# LiDAR_Lite_Interface_HardSwitch.net
KiCad netlist of a schematic drawn in EAGLE
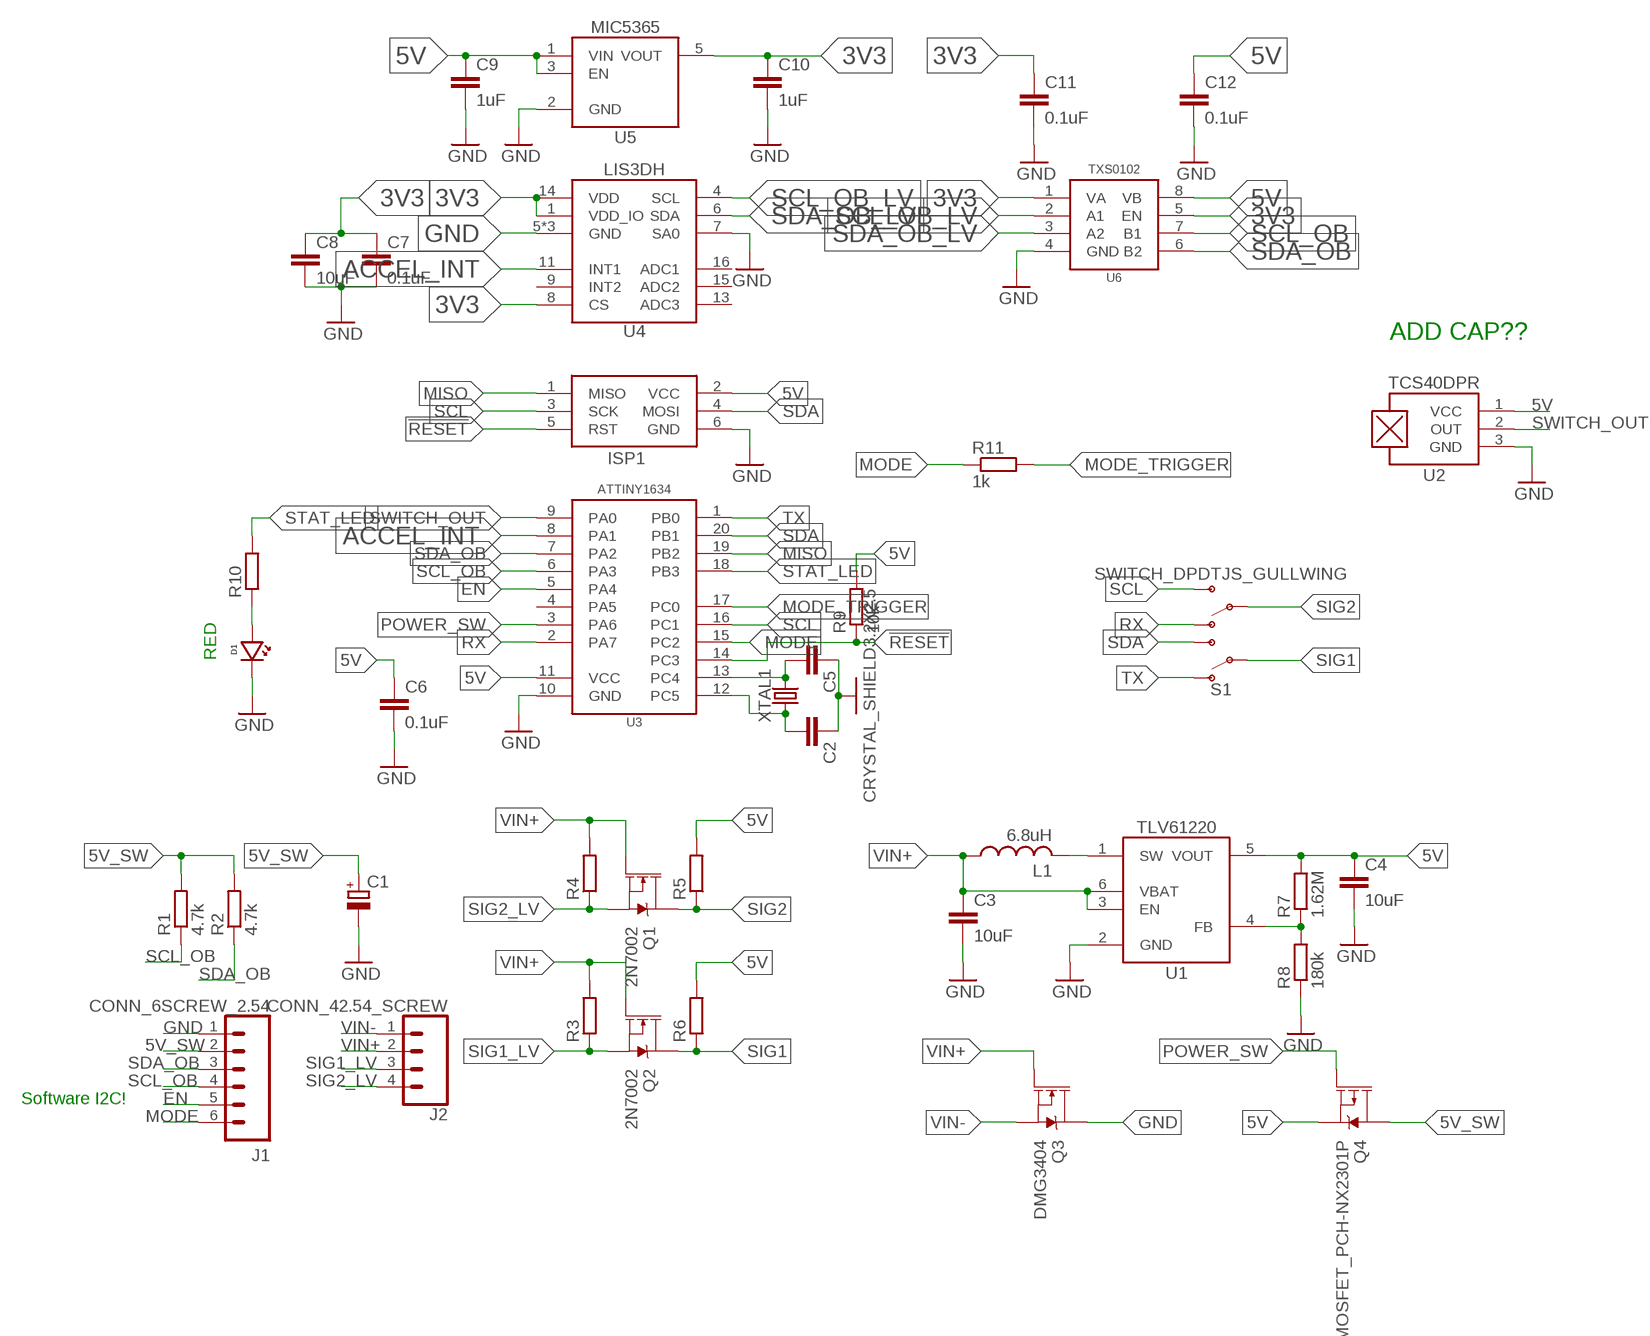
[diagram p0: schematic, sheet 1]

(export (version "E")
  (design (tool "Eeschema 10.0.6"))
  (components
    (comp (ref "C1")
      (value "CPOL-EUUW-10X10")
      (footprint "eagle-import:UW-10X10_NICHICON")
      (fields (field (name "MF") "Nichicon") (field (name "MPN") "UWT1C681MNL1GS"))
      (libsource (lib "eagle-import") (part "CPOL-EUUW-10X10"))
    )
    (comp (ref "C2")
      (value "C-EU10PFC0603")
      (footprint "eagle-import:C0603")
      (fields (field (name "MF") "Yageo") (field (name "MPN") "CC0603JRNPO9BN100CC0603JRNPO9BN100"))
      (libsource (lib "eagle-import") (part "C-EUC060310PF"))
    )
    (comp (ref "C3")
      (value "10uF")
      (footprint "eagle-import:C0805")
      (fields (field (name "MF") "Murata") (field (name "MPN") "GRM21BR61C106KE15K"))
      (libsource (lib "eagle-import") (part "C-EUC080510UF"))
    )
    (comp (ref "C4")
      (value "10uF")
      (footprint "eagle-import:C0805")
      (fields (field (name "MF") "Murata") (field (name "MPN") "GRM21BR61C106KE15K"))
      (libsource (lib "eagle-import") (part "C-EUC080510UF"))
    )
    (comp (ref "C5")
      (value "C-EU10PFC0603")
      (footprint "eagle-import:C0603")
      (fields (field (name "MF") "Yageo") (field (name "MPN") "CC0603JRNPO9BN100CC0603JRNPO9BN100"))
      (libsource (lib "eagle-import") (part "C-EUC060310PF"))
    )
    (comp (ref "C6")
      (value "0.1uF")
      (footprint "eagle-import:C0603")
      (fields (field (name "MF") "Murata") (field (name "MPN") "GCM188R71E104KA57D"))
      (libsource (lib "eagle-import") (part "C-EUC06030.1UF"))
    )
    (comp (ref "C7")
      (value "0.1uF")
      (footprint "eagle-import:C0805")
      (fields (field (name "MF") "Murata") (field (name "MPN") "GRM21BR61C106KE15K"))
      (libsource (lib "eagle-import") (part "C-EUC080510UF"))
    )
    (comp (ref "C8")
      (value "10uF")
      (footprint "eagle-import:C0603")
      (fields (field (name "MF") "Murata") (field (name "MPN") "GCM188R71E104KA57D"))
      (libsource (lib "eagle-import") (part "C-EUC06030.1UF"))
    )
    (comp (ref "C9")
      (value "1uF")
      (footprint "eagle-import:C0603")
      (fields (field (name "MF") "Murata") (field (name "MPN") "GRM188R61C105KA12D"))
      (libsource (lib "eagle-import") (part "C-EUC06031UF"))
    )
    (comp (ref "C10")
      (value "1uF")
      (footprint "eagle-import:C0603")
      (fields (field (name "MF") "Murata") (field (name "MPN") "GRM188R61C105KA12D"))
      (libsource (lib "eagle-import") (part "C-EUC06031UF"))
    )
    (comp (ref "C11")
      (value "0.1uF")
      (footprint "eagle-import:C0402")
      (fields (field (name "MF") "Murata") (field (name "MPN") "GCM155R71C104KA55D"))
      (libsource (lib "eagle-import") (part "C-EUC04020.1UF"))
    )
    (comp (ref "C12")
      (value "0.1uF")
      (footprint "eagle-import:C0402")
      (fields (field (name "MF") "Murata") (field (name "MPN") "GCM155R71C104KA55D"))
      (libsource (lib "eagle-import") (part "C-EUC04020.1UF"))
    )
    (comp (ref "D1")
      (value "LED0603")
      (footprint "eagle-import:LED_0603")
      (fields
        (field (name "DIGIKEY") "732-4978-1-ND")
        (field (name "MF") "Wurth")
        (field (name "MPN") "150060RS75000")
      )
      (libsource (lib "eagle-import") (part "LED0603"))
    )
    (comp (ref "ISP1")
      (value "AVRISP-6")
      (footprint "eagle-import:AVRISP")
      (libsource (lib "eagle-import") (part "AVRISP-6"))
    )
    (comp (ref "J1")
      (value "CONN_6SCREW_2.54")
      (footprint "eagle-import:1X06_SCREW")
      (fields (field (name "MF") "OnShore") (field (name "MPN") "OSTVN06A150"))
      (libsource (lib "eagle-import") (part "CONN_6SCREW_2.54"))
    )
    (comp (ref "J2")
      (value "CONN_42.54_SCREW")
      (footprint "eagle-import:1X04_SCREW")
      (fields (field (name "MF") "On Shore") (field (name "MPN") "OSTVN04A150"))
      (libsource (lib "eagle-import") (part "CONN_42.54_SCREW"))
    )
    (comp (ref "L1")
      (value "6.8uH")
      (footprint "eagle-import:1008")
      (fields (field (name "MF") "Wurth") (field (name "MPN") "74438323068"))
      (libsource (lib "eagle-import") (part "INDUCTOR1008"))
    )
    (comp (ref "Q1")
      (value "2N7002")
      (footprint "eagle-import:SOT23-3")
      (fields (field (name "MF") "Nexperia") (field (name "MPN") "2N7002P,215"))
      (libsource (lib "eagle-import") (part "MOSFET-NCH-2N7002P"))
    )
    (comp (ref "Q2")
      (value "2N7002")
      (footprint "eagle-import:SOT23-3")
      (fields (field (name "MF") "Nexperia") (field (name "MPN") "2N7002P,215"))
      (libsource (lib "eagle-import") (part "MOSFET-NCH-2N7002P"))
    )
    (comp (ref "Q3")
      (value "DMG3404")
      (footprint "eagle-import:SOT23-3")
      (fields (field (name "MF") "Diodes Incorporated") (field (name "MPN") "DMG3404L-7"))
      (libsource (lib "eagle-import") (part "MOSFET-NCH-DMG3404L"))
    )
    (comp (ref "Q4")
      (value "MOSFET_PCH-NX2301P")
      (footprint "eagle-import:SOT23-3")
      (fields (field (name "MF") "Nexperia") (field (name "MPN") "NX2301P,215"))
      (libsource (lib "eagle-import") (part "MOSFET_PCH-NX2301P"))
    )
    (comp (ref "R1")
      (value "4.7k")
      (footprint "eagle-import:R0603")
      (fields (field (name "MF") "Yageo") (field (name "MPN") "RC0603FR-074K7L"))
      (libsource (lib "eagle-import") (part "R-EU_R06034.7K"))
    )
    (comp (ref "R2")
      (value "4.7k")
      (footprint "eagle-import:R0603")
      (fields (field (name "MF") "Yageo") (field (name "MPN") "RC0603FR-074K7L"))
      (libsource (lib "eagle-import") (part "R-EU_R06034.7K"))
    )
    (comp (ref "R3")
      (value "R-EU_10KR0603")
      (footprint "eagle-import:R0603")
      (fields
        (field (name "MF") "Yageo")
        (field (name "MPN") "RC0603FR-0710KL")
        (field (name "VALUE_PART") "10k")
      )
      (libsource (lib "eagle-import") (part "R-EU_R060310K"))
    )
    (comp (ref "R4")
      (value "R-EU_10KR0603")
      (footprint "eagle-import:R0603")
      (fields
        (field (name "MF") "Yageo")
        (field (name "MPN") "RC0603FR-0710KL")
        (field (name "VALUE_PART") "10k")
      )
      (libsource (lib "eagle-import") (part "R-EU_R060310K"))
    )
    (comp (ref "R5")
      (value "R-EU_10KR0603")
      (footprint "eagle-import:R0603")
      (fields
        (field (name "MF") "Yageo")
        (field (name "MPN") "RC0603FR-0710KL")
        (field (name "VALUE_PART") "10k")
      )
      (libsource (lib "eagle-import") (part "R-EU_R060310K"))
    )
    (comp (ref "R6")
      (value "R-EU_10KR0603")
      (footprint "eagle-import:R0603")
      (fields
        (field (name "MF") "Yageo")
        (field (name "MPN") "RC0603FR-0710KL")
        (field (name "VALUE_PART") "10k")
      )
      (libsource (lib "eagle-import") (part "R-EU_R060310K"))
    )
    (comp (ref "R7")
      (value "1.62M")
      (footprint "eagle-import:R0603")
      (fields (field (name "MF") "Stackpole") (field (name "MPN") "RMCF0603FT1M62"))
      (libsource (lib "eagle-import") (part "R-EU_R06031.62M"))
    )
    (comp (ref "R8")
      (value "180k")
      (footprint "eagle-import:R0603")
      (fields (field (name "MF") "Panasonic") (field (name "MPN") "ERJ-3EKF1803V"))
      (libsource (lib "eagle-import") (part "R-EU_R0603180K"))
    )
    (comp (ref "R9")
      (value "10k")
      (footprint "eagle-import:R0603")
      (fields (field (name "MF") "Yageo") (field (name "MPN") "RC0603FR-0710KL"))
      (libsource (lib "eagle-import") (part "R-EU_R060310K"))
    )
    (comp (ref "R10")
      (value "R-EU_330R0603")
      (footprint "eagle-import:R0603")
      (fields
        (field (name "MF") "Yageo")
        (field (name "MPN") "RC0603FR-07330RL")
        (field (name "VALUE_PART") "330")
      )
      (libsource (lib "eagle-import") (part "R-EU_R0603330"))
    )
    (comp (ref "R11")
      (value "1k")
      (footprint "eagle-import:R0603")
      (fields (field (name "MF") "Yageo") (field (name "MPN") "AC0603FR-071KL"))
      (libsource (lib "eagle-import") (part "R-EU_R06031K"))
    )
    (comp (ref "S1")
      (value "SWITCH_DPDTJS_GULLWING")
      (footprint "eagle-import:JS202011SCQN")
      (fields (field (name "MF") "C&K") (field (name "MPN") "JS202011SCQN"))
      (libsource (lib "eagle-import") (part "SWITCH_DPDTJS_GULLWING"))
    )
    (comp (ref "U1")
      (value "TLV61220DBV")
      (footprint "eagle-import:DBV_R-PDSO-G6")
      (fields (field (name "MF") "TI") (field (name "MPN") "TLV61220DBVR"))
      (libsource (lib "eagle-import") (part "TLV61220DBV"))
    )
    (comp (ref "U2")
      (value "TCS40DPRSOT23")
      (footprint "eagle-import:SOT23-3")
      (fields
        (field (name "DISP") "TCS40DPR")
        (field (name "MF") "Toshiba")
        (field (name "MPN") "TCS40DPR,LF")
      )
      (libsource (lib "eagle-import") (part "TCS40DPRSOT23"))
    )
    (comp (ref "U3")
      (value "ATTINY1634SOIC")
      (footprint "eagle-import:SO-20DW")
      (fields (field (name "MF") "Atmel") (field (name "MPN") "ATTINY1634-SUR"))
      (libsource (lib "eagle-import") (part "ATTINY1634SOIC"))
    )
    (comp (ref "U4")
      (value "LIS3DHLGA")
      (footprint "eagle-import:LGA-16")
      (fields (field (name "MF") "ST") (field (name "MPN") "LIS3DHTR"))
      (libsource (lib "eagle-import") (part "LIS3DHLGA"))
    )
    (comp (ref "U5")
      (value "MIC53653.3SC70")
      (footprint "eagle-import:DCK_R-PDSO-G5")
      (fields (field (name "MF") "Microchip") (field (name "MPN") "MIC5365-3.3YC5-TR"))
      (libsource (lib "eagle-import") (part "MIC5365SC703.3"))
    )
    (comp (ref "U6")
      (value "TXS0102DQM")
      (footprint "eagle-import:DQM_R-PX2SON-N8")
      (fields (field (name "MF") "TI") (field (name "MPN") "TXS0102DQMR"))
      (libsource (lib "eagle-import") (part "TXS0102DQM"))
    )
    (comp (ref "XTAL1")
      (value "CRYSTAL_SHIELD3.2X2.5")
      (footprint "eagle-import:CRYSTAL_3.2X2.5_4-SMD")
      (fields (field (name "MF") "Abricon") (field (name "MPN") "ABM8G-12.000MHZ-4Y-T3"))
      (libsource (lib "eagle-import") (part "CRYSTAL_SHIELD3.2X2.5"))
    )
  )
  (nets
    (net (code "1") (name "/~{RESET}") (class "Default")
      (node (ref "ISP1") (pin "5") (pinfunction "RST_5") (pintype "output"))
      (node (ref "R9") (pin "1") (pinfunction "1_1") (pintype "passive"))
      (node (ref "U3") (pin "14") (pinfunction "PC3_14") (pintype "bidirectional"))
    )
    (net (code "2") (name "3V3") (class "Default")
      (node (ref "C10") (pin "1") (pinfunction "1_1") (pintype "passive"))
      (node (ref "C11") (pin "1") (pinfunction "1_1") (pintype "passive"))
      (node (ref "C7") (pin "1") (pinfunction "1_1") (pintype "passive"))
      (node (ref "C8") (pin "1") (pinfunction "1_1") (pintype "passive"))
      (node (ref "U4") (pin "1") (pinfunction "VDD_IO_1") (pintype "bidirectional"))
      (node (ref "U4") (pin "14") (pinfunction "VDD_14") (pintype "bidirectional"))
      (node (ref "U4") (pin "8") (pinfunction "CS_8") (pintype "bidirectional"))
      (node (ref "U5") (pin "5") (pinfunction "VOUT_5") (pintype "power_in"))
      (node (ref "U6") (pin "1") (pinfunction "VA_1") (pintype "power_in"))
      (node (ref "U6") (pin "5") (pinfunction "EN_5") (pintype "input"))
    )
    (net (code "3") (name "5V") (class "Default")
      (node (ref "C12") (pin "1") (pinfunction "1_1") (pintype "passive"))
      (node (ref "C4") (pin "1") (pinfunction "1_1") (pintype "passive"))
      (node (ref "C6") (pin "1") (pinfunction "1_1") (pintype "passive"))
      (node (ref "C9") (pin "1") (pinfunction "1_1") (pintype "passive"))
      (node (ref "ISP1") (pin "2") (pinfunction "VCC_2") (pintype "power_in"))
      (node (ref "Q4") (pin "2") (pinfunction "S_2") (pintype "bidirectional"))
      (node (ref "R5") (pin "2") (pinfunction "2_2") (pintype "passive"))
      (node (ref "R6") (pin "2") (pinfunction "2_2") (pintype "passive"))
      (node (ref "R7") (pin "2") (pinfunction "2_2") (pintype "passive"))
      (node (ref "R9") (pin "2") (pinfunction "2_2") (pintype "passive"))
      (node (ref "U1") (pin "5") (pinfunction "VOUT_5") (pintype "power_in"))
      (node (ref "U2") (pin "1") (pinfunction "VCC_1") (pintype "power_in"))
      (node (ref "U3") (pin "11") (pinfunction "VCC_11") (pintype "power_in"))
      (node (ref "U5") (pin "1") (pinfunction "VIN_1") (pintype "power_in"))
      (node (ref "U5") (pin "3") (pinfunction "EN_3") (pintype "input"))
      (node (ref "U6") (pin "8") (pinfunction "VB_8") (pintype "power_in"))
    )
    (net (code "4") (name "5V_SW") (class "Default")
      (node (ref "C1") (pin "+") (pinfunction "+_+") (pintype "passive"))
      (node (ref "J1") (pin "2") (pinfunction "2_2") (pintype "passive"))
      (node (ref "Q4") (pin "3") (pinfunction "D_3") (pintype "bidirectional"))
      (node (ref "R1") (pin "2") (pinfunction "2_2") (pintype "passive"))
      (node (ref "R2") (pin "2") (pinfunction "2_2") (pintype "passive"))
    )
    (net (code "5") (name "ACCEL_INT") (class "Default")
      (node (ref "U3") (pin "8") (pinfunction "PA1_8") (pintype "bidirectional"))
      (node (ref "U4") (pin "11") (pinfunction "INT1_11") (pintype "bidirectional"))
    )
    (net (code "6") (name "EN") (class "Default")
      (node (ref "J1") (pin "5") (pinfunction "5_5") (pintype "passive"))
      (node (ref "U3") (pin "5") (pinfunction "PA4_5") (pintype "bidirectional"))
    )
    (net (code "7") (name "GND") (class "Default")
      (node (ref "C1") (pin "-") (pinfunction "-_-") (pintype "passive"))
      (node (ref "C10") (pin "2") (pinfunction "2_2") (pintype "passive"))
      (node (ref "C11") (pin "2") (pinfunction "2_2") (pintype "passive"))
      (node (ref "C12") (pin "2") (pinfunction "2_2") (pintype "passive"))
      (node (ref "C2") (pin "1") (pinfunction "1_1") (pintype "passive"))
      (node (ref "C3") (pin "2") (pinfunction "2_2") (pintype "passive"))
      (node (ref "C4") (pin "2") (pinfunction "2_2") (pintype "passive"))
      (node (ref "C5") (pin "1") (pinfunction "1_1") (pintype "passive"))
      (node (ref "C6") (pin "2") (pinfunction "2_2") (pintype "passive"))
      (node (ref "C7") (pin "2") (pinfunction "2_2") (pintype "passive"))
      (node (ref "C8") (pin "2") (pinfunction "2_2") (pintype "passive"))
      (node (ref "C9") (pin "2") (pinfunction "2_2") (pintype "passive"))
      (node (ref "D1") (pin "CATHODE") (pinfunction "CATHODE_CATHODE") (pintype "power_in"))
      (node (ref "ISP1") (pin "6") (pinfunction "GND_6") (pintype "power_in"))
      (node (ref "J1") (pin "1") (pinfunction "1_1") (pintype "passive"))
      (node (ref "Q3") (pin "3") (pinfunction "D_3") (pintype "bidirectional"))
      (node (ref "R8") (pin "1") (pinfunction "1_1") (pintype "passive"))
      (node (ref "U1") (pin "2") (pinfunction "GND_2") (pintype "power_in"))
      (node (ref "U2") (pin "3") (pinfunction "GND_3") (pintype "power_in"))
      (node (ref "U3") (pin "10") (pinfunction "GND_10") (pintype "power_in"))
      (node (ref "U4") (pin "10") (pinfunction "GND_10") (pintype "bidirectional"))
      (node (ref "U4") (pin "12") (pinfunction "GND_12") (pintype "bidirectional"))
      (node (ref "U4") (pin "5") (pinfunction "GND_5") (pintype "bidirectional"))
      (node (ref "U4") (pin "7") (pinfunction "SA0_7") (pintype "bidirectional"))
      (node (ref "U5") (pin "2") (pinfunction "GND_2") (pintype "power_in"))
      (node (ref "U6") (pin "4") (pinfunction "GND_4") (pintype "power_in"))
      (node (ref "XTAL1") (pin "2") (pinfunction "GND_2") (pintype "power_in"))
      (node (ref "XTAL1") (pin "4") (pinfunction "GND_4") (pintype "power_in"))
    )
    (net (code "8") (name "MISO") (class "Default")
      (node (ref "ISP1") (pin "1") (pinfunction "MISO_1") (pintype "input"))
      (node (ref "U3") (pin "19") (pinfunction "PB2_19") (pintype "bidirectional"))
    )
    (net (code "9") (name "MODE") (class "Default")
      (node (ref "J1") (pin "6") (pinfunction "6_6") (pintype "passive"))
      (node (ref "R11") (pin "1") (pinfunction "1_1") (pintype "passive"))
      (node (ref "U3") (pin "15") (pinfunction "PC2_15") (pintype "bidirectional"))
    )
    (net (code "10") (name "MODE_TRIGGER") (class "Default")
      (node (ref "R11") (pin "2") (pinfunction "2_2") (pintype "passive"))
      (node (ref "U3") (pin "17") (pinfunction "PC0_17") (pintype "bidirectional"))
    )
    (net (code "11") (name "Net-(D1-PadANODE)") (class "Default")
      (node (ref "D1") (pin "ANODE") (pinfunction "ANODE_ANODE") (pintype "power_in"))
      (node (ref "R10") (pin "1") (pinfunction "1_1") (pintype "passive"))
    )
    (net (code "12") (name "Net-(U1-FB)") (class "Default")
      (node (ref "R7") (pin "1") (pinfunction "1_1") (pintype "passive"))
      (node (ref "R8") (pin "2") (pinfunction "2_2") (pintype "passive"))
      (node (ref "U1") (pin "4") (pinfunction "FB_4") (pintype "input"))
    )
    (net (code "13") (name "Net-(U1-SW)") (class "Default")
      (node (ref "L1") (pin "2") (pinfunction "2_2") (pintype "passive"))
      (node (ref "U1") (pin "1") (pinfunction "SW_1") (pintype "power_in"))
    )
    (net (code "14") (name "Net-(U3-PC4)") (class "Default")
      (node (ref "C5") (pin "2") (pinfunction "2_2") (pintype "passive"))
      (node (ref "U3") (pin "13") (pinfunction "PC4_13") (pintype "bidirectional"))
      (node (ref "XTAL1") (pin "3") (pinfunction "2_3") (pintype "passive"))
    )
    (net (code "15") (name "Net-(U3-PC5)") (class "Default")
      (node (ref "C2") (pin "2") (pinfunction "2_2") (pintype "passive"))
      (node (ref "U3") (pin "12") (pinfunction "PC5_12") (pintype "bidirectional"))
      (node (ref "XTAL1") (pin "1") (pinfunction "1_1") (pintype "passive"))
    )
    (net (code "16") (name "POWER_SW") (class "Default")
      (node (ref "Q4") (pin "1") (pinfunction "G_1") (pintype "bidirectional"))
      (node (ref "U3") (pin "3") (pinfunction "PA6_3") (pintype "bidirectional"))
    )
    (net (code "17") (name "RX") (class "Default")
      (node (ref "S1") (pin "6") (pinfunction "O2_6") (pintype "passive"))
      (node (ref "U3") (pin "2") (pinfunction "PA7_2") (pintype "bidirectional"))
    )
    (net (code "18") (name "SCL") (class "Default")
      (node (ref "ISP1") (pin "3") (pinfunction "SCK_3") (pintype "output"))
      (node (ref "S1") (pin "4") (pinfunction "S2_4") (pintype "passive"))
      (node (ref "U3") (pin "16") (pinfunction "PC1_16") (pintype "bidirectional"))
    )
    (net (code "19") (name "SCL_OB") (class "Default")
      (node (ref "J1") (pin "4") (pinfunction "4_4") (pintype "passive"))
      (node (ref "R1") (pin "1") (pinfunction "1_1") (pintype "passive"))
      (node (ref "U3") (pin "6") (pinfunction "PA3_6") (pintype "bidirectional"))
      (node (ref "U6") (pin "7") (pinfunction "B1_7") (pintype "bidirectional"))
    )
    (net (code "20") (name "SCL_OB_LV") (class "Default")
      (node (ref "U4") (pin "4") (pinfunction "SCL_4") (pintype "bidirectional"))
      (node (ref "U6") (pin "2") (pinfunction "A1_2") (pintype "bidirectional"))
    )
    (net (code "21") (name "SDA") (class "Default")
      (node (ref "ISP1") (pin "4") (pinfunction "MOSI_4") (pintype "output"))
      (node (ref "S1") (pin "3") (pinfunction "S1_3") (pintype "passive"))
      (node (ref "U3") (pin "20") (pinfunction "PB1_20") (pintype "bidirectional"))
    )
    (net (code "22") (name "SDA_OB") (class "Default")
      (node (ref "J1") (pin "3") (pinfunction "3_3") (pintype "passive"))
      (node (ref "R2") (pin "1") (pinfunction "1_1") (pintype "passive"))
      (node (ref "U3") (pin "7") (pinfunction "PA2_7") (pintype "bidirectional"))
      (node (ref "U6") (pin "6") (pinfunction "B2_6") (pintype "bidirectional"))
    )
    (net (code "23") (name "SDA_OB_LV") (class "Default")
      (node (ref "U4") (pin "6") (pinfunction "SDA_6") (pintype "bidirectional"))
      (node (ref "U6") (pin "3") (pinfunction "A2_3") (pintype "bidirectional"))
    )
    (net (code "24") (name "SIG1") (class "Default")
      (node (ref "Q2") (pin "3") (pinfunction "D_3") (pintype "bidirectional"))
      (node (ref "R6") (pin "1") (pinfunction "1_1") (pintype "passive"))
      (node (ref "S1") (pin "2") (pinfunction "P1_2") (pintype "passive"))
    )
    (net (code "25") (name "SIG1_LV") (class "Default")
      (node (ref "J2") (pin "3") (pinfunction "3_3") (pintype "passive"))
      (node (ref "Q2") (pin "2") (pinfunction "S_2") (pintype "bidirectional"))
      (node (ref "R3") (pin "1") (pinfunction "1_1") (pintype "passive"))
    )
    (net (code "26") (name "SIG2") (class "Default")
      (node (ref "Q1") (pin "3") (pinfunction "D_3") (pintype "bidirectional"))
      (node (ref "R5") (pin "1") (pinfunction "1_1") (pintype "passive"))
      (node (ref "S1") (pin "5") (pinfunction "P2_5") (pintype "passive"))
    )
    (net (code "27") (name "SIG2_LV") (class "Default")
      (node (ref "J2") (pin "4") (pinfunction "4_4") (pintype "passive"))
      (node (ref "Q1") (pin "2") (pinfunction "S_2") (pintype "bidirectional"))
      (node (ref "R4") (pin "1") (pinfunction "1_1") (pintype "passive"))
    )
    (net (code "28") (name "STAT_LED") (class "Default")
      (node (ref "R10") (pin "2") (pinfunction "2_2") (pintype "passive"))
      (node (ref "U3") (pin "18") (pinfunction "PB3_18") (pintype "bidirectional"))
    )
    (net (code "29") (name "SWITCH_OUT") (class "Default")
      (node (ref "U2") (pin "2") (pinfunction "OUT_2") (pintype "output"))
      (node (ref "U3") (pin "9") (pinfunction "PA0_9") (pintype "bidirectional"))
    )
    (net (code "30") (name "TX") (class "Default")
      (node (ref "S1") (pin "1") (pinfunction "O1_1") (pintype "passive"))
      (node (ref "U3") (pin "1") (pinfunction "PB0_1") (pintype "bidirectional"))
    )
    (net (code "31") (name "VIN+") (class "Default")
      (node (ref "C3") (pin "1") (pinfunction "1_1") (pintype "passive"))
      (node (ref "J2") (pin "2") (pinfunction "2_2") (pintype "passive"))
      (node (ref "L1") (pin "1") (pinfunction "1_1") (pintype "passive"))
      (node (ref "Q1") (pin "1") (pinfunction "G_1") (pintype "bidirectional"))
      (node (ref "Q2") (pin "1") (pinfunction "G_1") (pintype "bidirectional"))
      (node (ref "Q3") (pin "1") (pinfunction "G_1") (pintype "bidirectional"))
      (node (ref "R3") (pin "2") (pinfunction "2_2") (pintype "passive"))
      (node (ref "R4") (pin "2") (pinfunction "2_2") (pintype "passive"))
      (node (ref "U1") (pin "3") (pinfunction "EN_3") (pintype "input"))
      (node (ref "U1") (pin "6") (pinfunction "VBAT_6") (pintype "power_in"))
    )
    (net (code "32") (name "VIN-") (class "Default")
      (node (ref "J2") (pin "1") (pinfunction "1_1") (pintype "passive"))
      (node (ref "Q3") (pin "2") (pinfunction "S_2") (pintype "bidirectional"))
    )
    (net (code "33") (name "unconnected-(U3-PA5-Pad4)") (class "Default")
      (node (ref "U3") (pin "4") (pinfunction "PA5_4") (pintype "bidirectional"))
    )
    (net (code "34") (name "unconnected-(U4-ADC1-Pad16)") (class "Default")
      (node (ref "U4") (pin "16") (pinfunction "ADC1_16") (pintype "bidirectional"))
    )
    (net (code "35") (name "unconnected-(U4-ADC2-Pad15)") (class "Default")
      (node (ref "U4") (pin "15") (pinfunction "ADC2_15") (pintype "bidirectional"))
    )
    (net (code "36") (name "unconnected-(U4-ADC3-Pad13)") (class "Default")
      (node (ref "U4") (pin "13") (pinfunction "ADC3_13") (pintype "bidirectional"))
    )
    (net (code "37") (name "unconnected-(U4-INT2-Pad9)") (class "Default")
      (node (ref "U4") (pin "9") (pinfunction "INT2_9") (pintype "bidirectional"))
    )
  )
)
